# SensorConn.net
KiCad netlist of a schematic drawn in Altium Designer
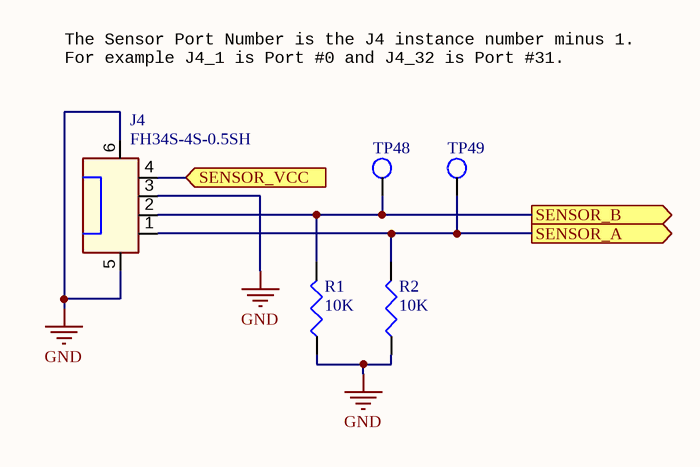
[diagram p0: SensorConn.SchDoc]

(export (version "E")
  (design (tool "Eeschema 10.0.6"))
  (components
    (comp (ref "J4")
      (value "FH34S-4S-0.5SH")
      (footprint "con_hirose_FH34SRJ-4S")
      (description "CONN FFC FPC 4POS 0.50MM R/A")
      (fields (field (name "MFG") "HIROSE"))
      (libsource (lib "SynapseLibrary") (part "HEADER 4 TABS"))
    )
    (comp (ref "R1")
      (value "10K")
      (footprint "0402-IPCsm_40")
      (description "RES 10.0K OHM 1/16W 5% 0402 SMD")
      (fields (field (name "TOLERANCE") "5.00%") (field (name "VOLTAGE") "50V"))
      (libsource (lib "SynapseLibrary") (part "RES"))
    )
    (comp (ref "R2")
      (value "10K")
      (footprint "0402-IPCsm_40")
      (description "RES 10.0K OHM 1/16W 5% 0402 SMD")
      (fields (field (name "TOLERANCE") "5.00%") (field (name "VOLTAGE") "50V"))
      (libsource (lib "SynapseLibrary") (part "RES"))
    )
    (comp (ref "TP48")
      (value "tp-1mm")
      (footprint "TP-S100_SMT")
      (description "TESTPOINT, 1MM SMD, Square pad, Round SM opening")
      (fields (field (name "MFG") "NA"))
      (libsource (lib "SynapseLibrary") (part "tp_smt"))
    )
    (comp (ref "TP49")
      (value "tp-1mm")
      (footprint "TP-S100_SMT")
      (description "TESTPOINT, 1MM SMD, Square pad, Round SM opening")
      (fields (field (name "MFG") "NA"))
      (libsource (lib "SynapseLibrary") (part "tp_smt"))
    )
  )
  (nets
    (net (code "1") (name "/SENSOR_A") (class "Default")
      (node (ref "J4") (pin "1") (pinfunction "1_1") (pintype "passive"))
      (node (ref "R2") (pin "2") (pinfunction "2_2") (pintype "passive"))
      (node (ref "TP49") (pin "1") (pinfunction "TP_1") (pintype "passive"))
    )
    (net (code "2") (name "/SENSOR_B") (class "Default")
      (node (ref "J4") (pin "2") (pinfunction "2_2") (pintype "passive"))
      (node (ref "R1") (pin "2") (pinfunction "2_2") (pintype "passive"))
      (node (ref "TP48") (pin "1") (pinfunction "TP_1") (pintype "passive"))
    )
    (net (code "3") (name "/SENSOR_VCC") (class "Default")
      (node (ref "J4") (pin "4") (pinfunction "4_4") (pintype "passive"))
    )
    (net (code "4") (name "GND") (class "Default")
      (node (ref "J4") (pin "3") (pinfunction "3_3") (pintype "passive"))
      (node (ref "J4") (pin "5") (pinfunction "TAB1_5") (pintype "passive"))
      (node (ref "J4") (pin "6") (pinfunction "TAB2_6") (pintype "passive"))
      (node (ref "R1") (pin "1") (pinfunction "1_1") (pintype "passive"))
      (node (ref "R2") (pin "1") (pinfunction "1_1") (pintype "passive"))
    )
  )
)
